# JediLightSwitch.net
KiCad netlist of a schematic drawn in EAGLE
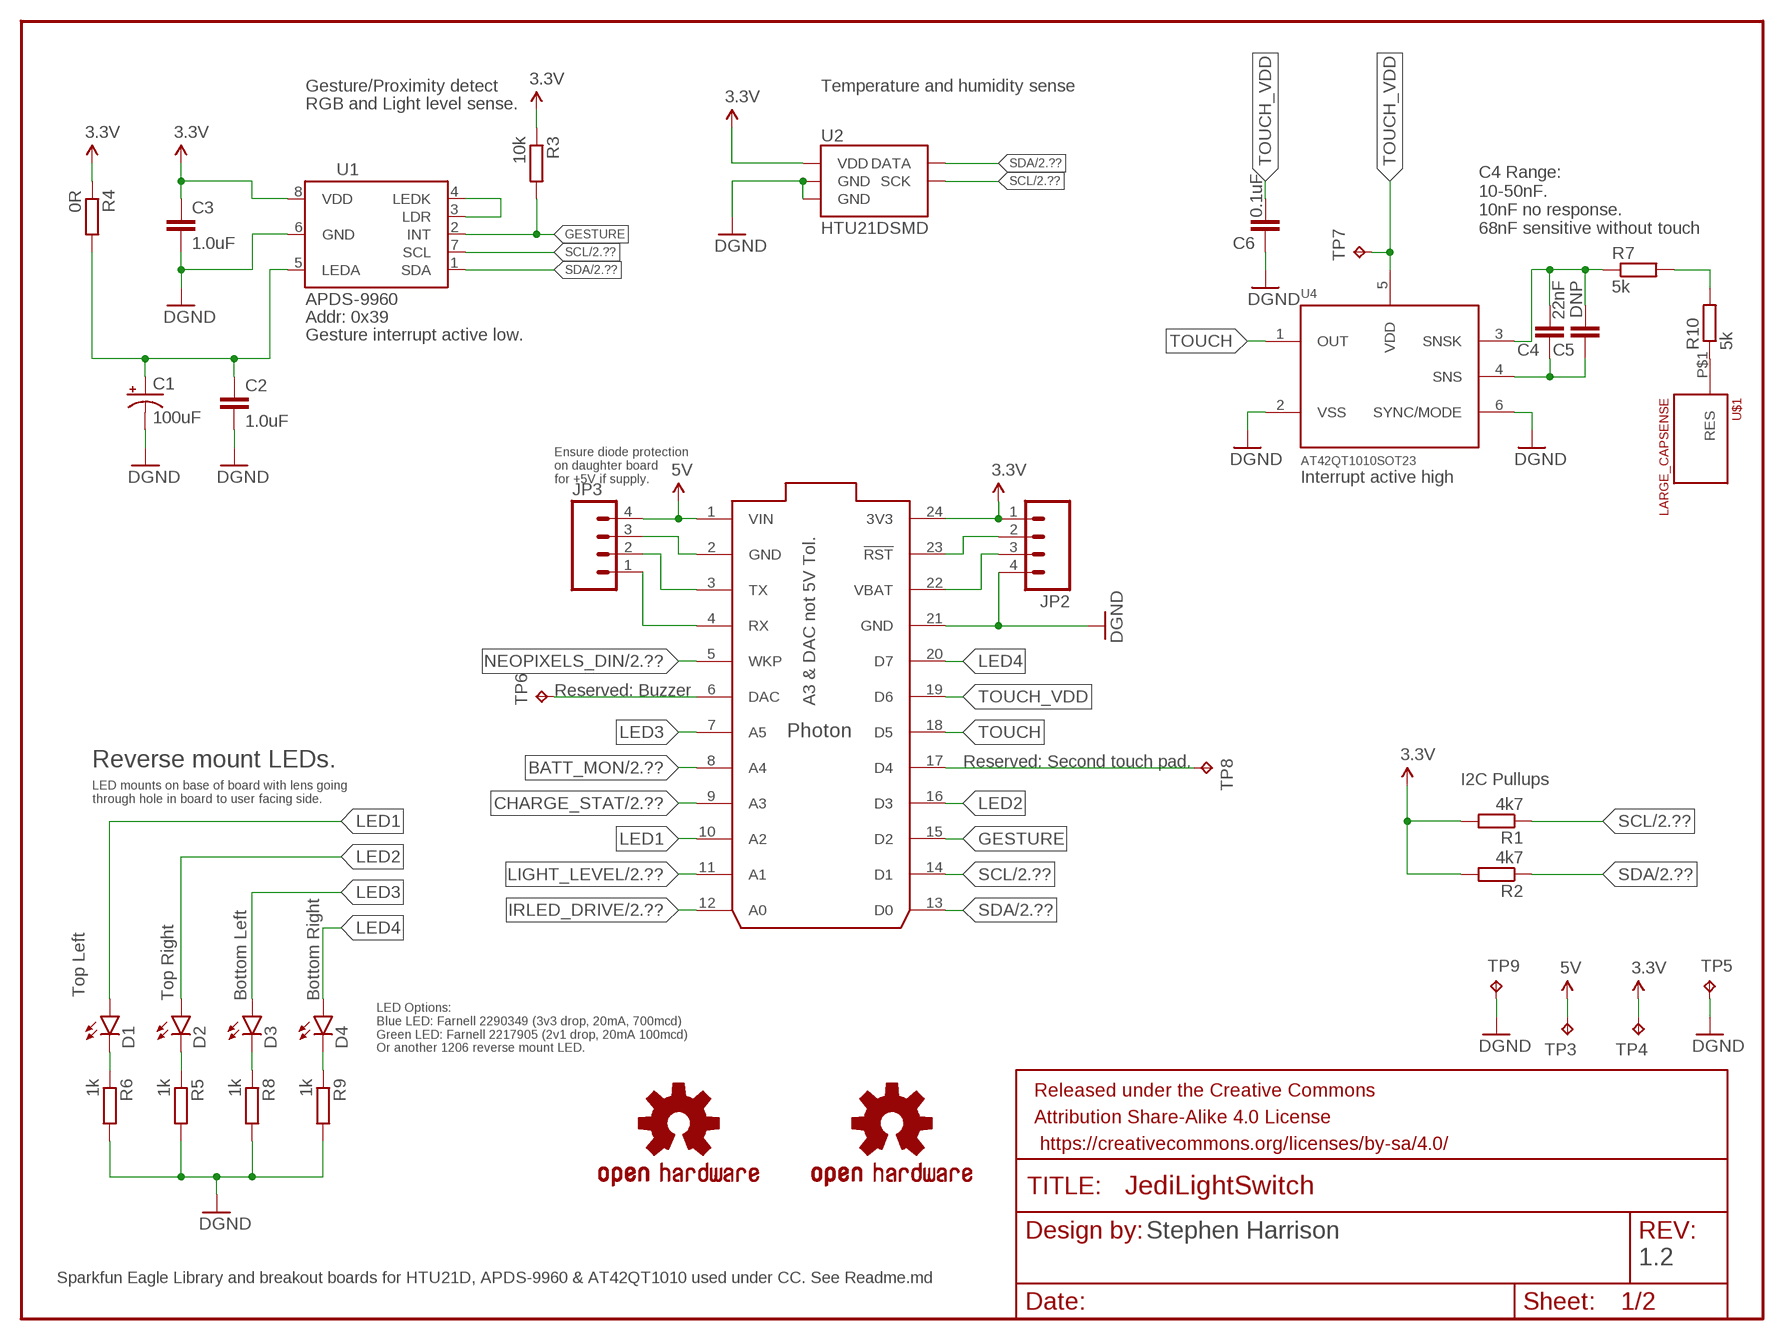
[diagram p0: schematic, sheet 1]
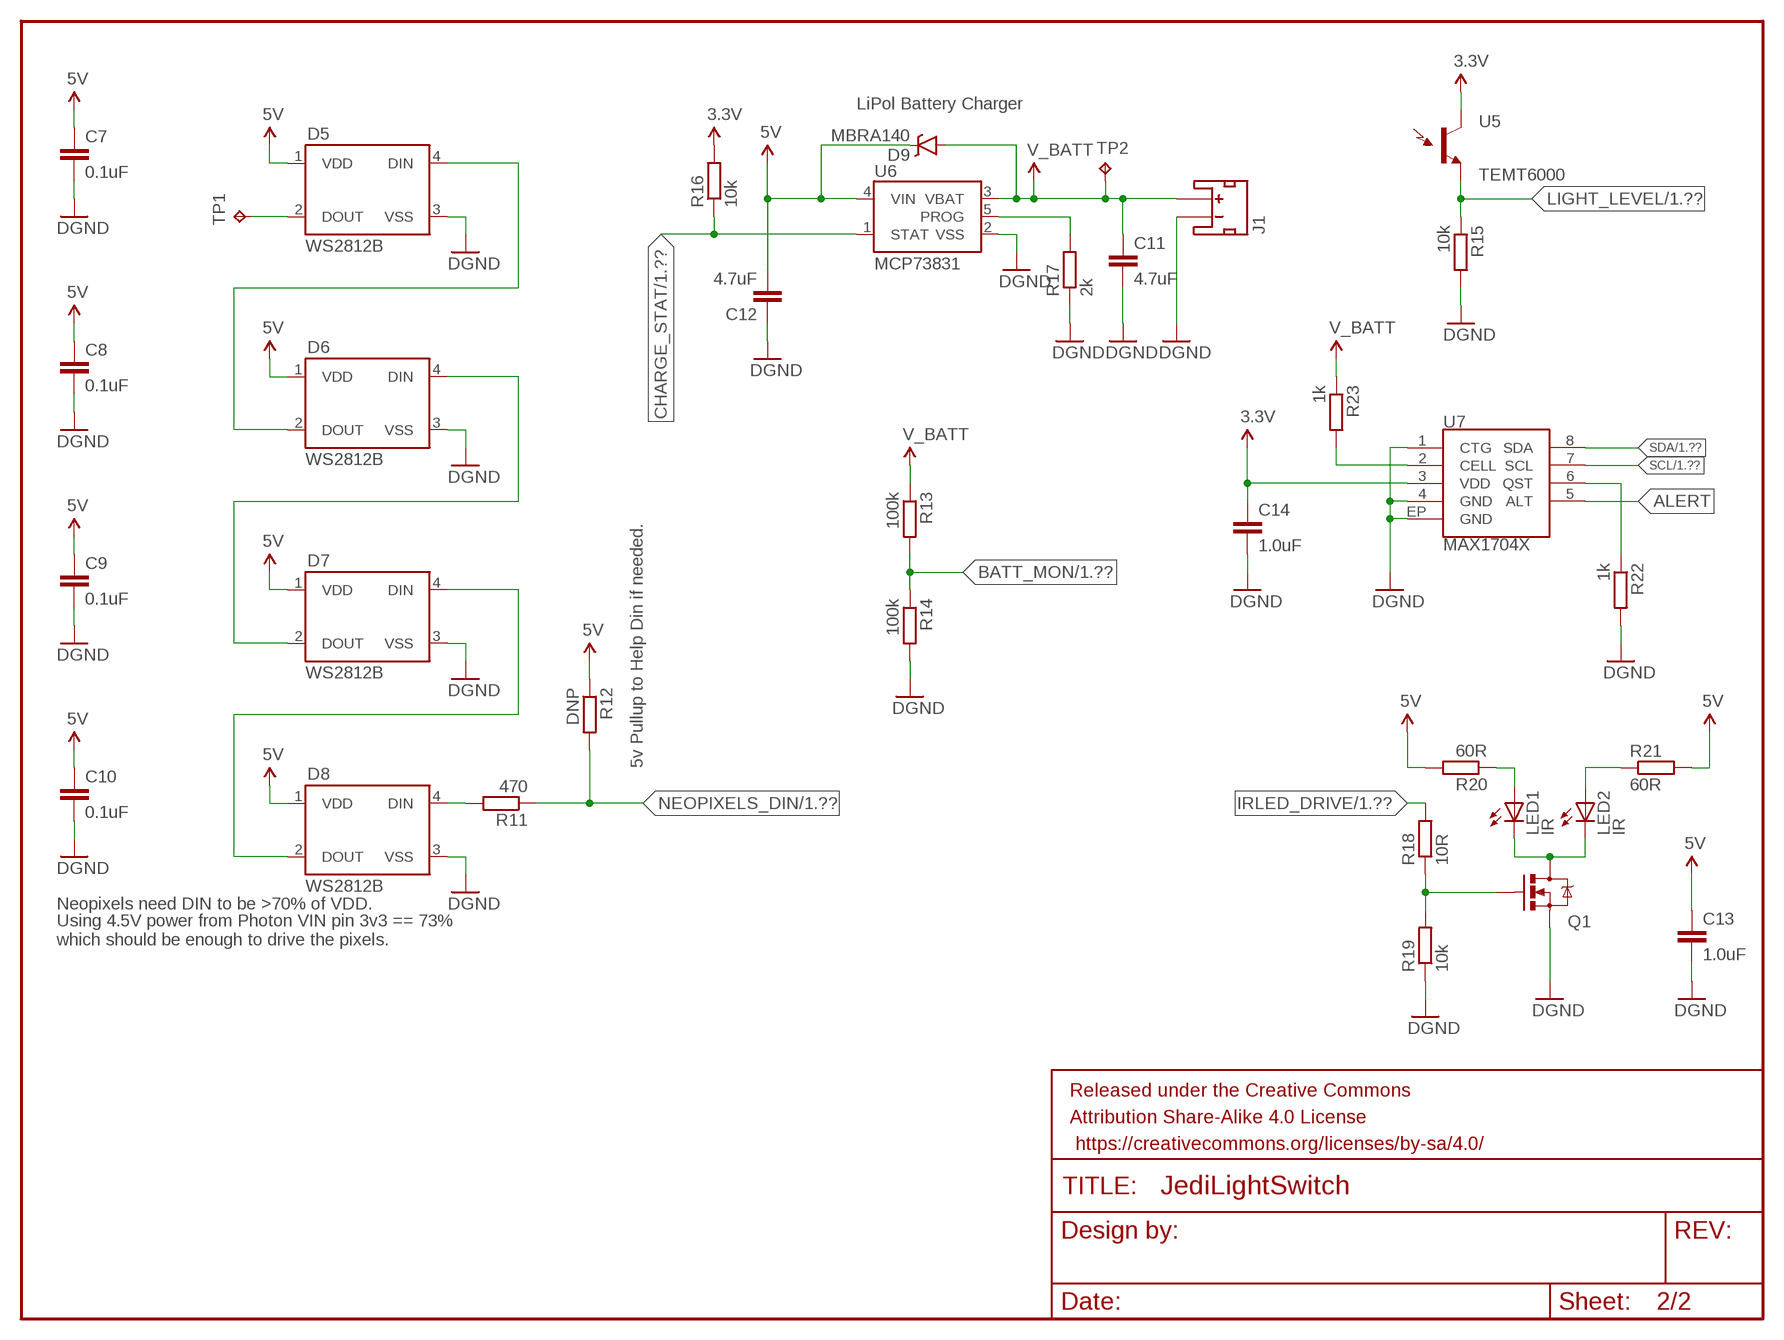
[diagram p1: schematic, sheet 2]

(export (version "E")
  (design (tool "Eeschema 10.0.6"))
  (components
    (comp (ref "C7")
      (value "0.1uF")
      (footprint "eagle-import:C0805")
      (libsource (lib "eagle-import") (part "C-EUC0805"))
    )
    (comp (ref "C8")
      (value "0.1uF")
      (footprint "eagle-import:C0805")
      (libsource (lib "eagle-import") (part "C-EUC0805"))
    )
    (comp (ref "C9")
      (value "0.1uF")
      (footprint "eagle-import:C0805")
      (libsource (lib "eagle-import") (part "C-EUC0805"))
    )
    (comp (ref "C10")
      (value "0.1uF")
      (footprint "eagle-import:C0805")
      (libsource (lib "eagle-import") (part "C-EUC0805"))
    )
    (comp (ref "C11")
      (value "4.7uF")
      (footprint "eagle-import:C0805")
      (libsource (lib "eagle-import") (part "C-EUC0805"))
    )
    (comp (ref "C12")
      (value "4.7uF")
      (footprint "eagle-import:C0805")
      (libsource (lib "eagle-import") (part "C-EUC0805"))
    )
    (comp (ref "C13")
      (value "1.0uF")
      (footprint "eagle-import:C0805")
      (libsource (lib "eagle-import") (part "C-EUC0805"))
    )
    (comp (ref "C14")
      (value "1.0uF")
      (footprint "eagle-import:C0805")
      (libsource (lib "eagle-import") (part "C-EUC0805"))
    )
    (comp (ref "D5")
      (value "WS2812B")
      (footprint "eagle-import:WS2812B")
      (libsource (lib "eagle-import") (part "WS2812B"))
    )
    (comp (ref "D6")
      (value "WS2812B")
      (footprint "eagle-import:WS2812B")
      (libsource (lib "eagle-import") (part "WS2812B"))
    )
    (comp (ref "D7")
      (value "WS2812B")
      (footprint "eagle-import:WS2812B")
      (libsource (lib "eagle-import") (part "WS2812B"))
    )
    (comp (ref "D8")
      (value "WS2812B")
      (footprint "eagle-import:WS2812B")
      (libsource (lib "eagle-import") (part "WS2812B"))
    )
    (comp (ref "D9")
      (value "MBRA140")
      (footprint "eagle-import:SMA-DIODE")
      (libsource (lib "eagle-import") (part "MBRA140"))
    )
    (comp (ref "FRAME1")
      (value "FRAME-LETTERNO_PACKAGE")
      (footprint "eagle-import:DUMMY")
      (fields (field (name "DESIGNER") "Nobody"))
      (libsource (lib "eagle-import") (part "FRAME-LETTERNO_PACKAGE"))
    )
    (comp (ref "J1")
      (value "JST_2MM_MALE")
      (footprint "eagle-import:JST-2-SMD")
      (libsource (lib "eagle-import") (part "JST_2MM_MALE"))
    )
    (comp (ref "LED1")
      (value "IR")
      (footprint "eagle-import:1206")
      (libsource (lib "eagle-import") (part "LEDSMT1206"))
    )
    (comp (ref "LED2")
      (value "IR")
      (footprint "eagle-import:1206")
      (libsource (lib "eagle-import") (part "LEDSMT1206"))
    )
    (comp (ref "Q1")
      (value "MOSFET-NCHANNELAO3404A")
      (footprint "eagle-import:SOT23-3")
      (libsource (lib "eagle-import") (part "MOSFET-NCHANNELAO3404A"))
    )
    (comp (ref "R11")
      (value "470")
      (footprint "eagle-import:R0805")
      (libsource (lib "eagle-import") (part "R-EU_R0805"))
    )
    (comp (ref "R12")
      (value "DNP")
      (footprint "eagle-import:R0805")
      (libsource (lib "eagle-import") (part "R-EU_R0805"))
    )
    (comp (ref "R13")
      (value "100k")
      (footprint "eagle-import:R0805")
      (libsource (lib "eagle-import") (part "R-EU_R0805"))
    )
    (comp (ref "R14")
      (value "100k")
      (footprint "eagle-import:R0805")
      (libsource (lib "eagle-import") (part "R-EU_R0805"))
    )
    (comp (ref "R15")
      (value "10k")
      (footprint "eagle-import:R0805")
      (libsource (lib "eagle-import") (part "R-EU_R0805"))
    )
    (comp (ref "R16")
      (value "10k")
      (footprint "eagle-import:R0805")
      (libsource (lib "eagle-import") (part "R-EU_R0805"))
    )
    (comp (ref "R17")
      (value "2k")
      (footprint "eagle-import:R0805")
      (libsource (lib "eagle-import") (part "R-EU_R0805"))
    )
    (comp (ref "R18")
      (value "10R")
      (footprint "eagle-import:R0805")
      (libsource (lib "eagle-import") (part "R-EU_R0805"))
    )
    (comp (ref "R19")
      (value "10k")
      (footprint "eagle-import:R0805")
      (libsource (lib "eagle-import") (part "R-EU_R0805"))
    )
    (comp (ref "R20")
      (value "60R")
      (footprint "eagle-import:R0805")
      (libsource (lib "eagle-import") (part "R-EU_R0805"))
    )
    (comp (ref "R21")
      (value "60R")
      (footprint "eagle-import:R0805")
      (libsource (lib "eagle-import") (part "R-EU_R0805"))
    )
    (comp (ref "R22")
      (value "1k")
      (footprint "eagle-import:R0805")
      (libsource (lib "eagle-import") (part "R-EU_R0805"))
    )
    (comp (ref "R23")
      (value "1k")
      (footprint "eagle-import:R0805")
      (libsource (lib "eagle-import") (part "R-EU_R0805"))
    )
    (comp (ref "TP1")
      (value "TPTP20R")
      (footprint "eagle-import:TP20R")
      (libsource (lib "eagle-import") (part "TPTP20R"))
    )
    (comp (ref "TP2")
      (value "TPTP20R")
      (footprint "eagle-import:TP20R")
      (libsource (lib "eagle-import") (part "TPTP20R"))
    )
    (comp (ref "U5")
      (value "TEMT6000")
      (footprint "eagle-import:TEMT6000-SEN")
      (libsource (lib "eagle-import") (part "LIGHTSENSORTEMT6000"))
    )
    (comp (ref "U6")
      (value "MCP73831")
      (footprint "eagle-import:SOT23-5")
      (libsource (lib "eagle-import") (part "MCP73831"))
    )
    (comp (ref "U7")
      (value "MAX1704X")
      (footprint "eagle-import:TDFN-8")
      (libsource (lib "eagle-import") (part "MAX1704X"))
    )
    (comp (ref "C1")
      (value "100uF")
      (footprint "eagle-import:EIA7343")
      (libsource (lib "eagle-import") (part "100UF-10V-10%(TANT)"))
    )
    (comp (ref "C2")
      (value "1.0uF")
      (footprint "eagle-import:C0805")
      (libsource (lib "eagle-import") (part "C-EUC0805"))
    )
    (comp (ref "C3")
      (value "1.0uF")
      (footprint "eagle-import:C0805")
      (libsource (lib "eagle-import") (part "C-EUC0805"))
    )
    (comp (ref "C4")
      (value "22nF")
      (footprint "eagle-import:C0805")
      (libsource (lib "eagle-import") (part "C-EUC0805"))
    )
    (comp (ref "C5")
      (value "DNP")
      (footprint "eagle-import:C0805")
      (libsource (lib "eagle-import") (part "C-EUC0805"))
    )
    (comp (ref "C6")
      (value "0.1uF")
      (footprint "eagle-import:C0805")
      (libsource (lib "eagle-import") (part "C-EUC0805"))
    )
    (comp (ref "D1")
      (value "LED1206-BOTTOM")
      (footprint "eagle-import:LED-1206-BOTTOM")
      (libsource (lib "eagle-import") (part "LED1206-BOTTOM"))
    )
    (comp (ref "D2")
      (value "LED1206-BOTTOM")
      (footprint "eagle-import:LED-1206-BOTTOM")
      (libsource (lib "eagle-import") (part "LED1206-BOTTOM"))
    )
    (comp (ref "D3")
      (value "LED1206-BOTTOM")
      (footprint "eagle-import:LED-1206-BOTTOM")
      (libsource (lib "eagle-import") (part "LED1206-BOTTOM"))
    )
    (comp (ref "D4")
      (value "LED1206-BOTTOM")
      (footprint "eagle-import:LED-1206-BOTTOM")
      (libsource (lib "eagle-import") (part "LED1206-BOTTOM"))
    )
    (comp (ref "FRAME2")
      (value "FRAME-LETTER")
      (footprint "eagle-import:CREATIVE_COMMONS")
      (libsource (lib "eagle-import") (part "FRAME-LETTER"))
    )
    (comp (ref "JP2")
      (value "M04SMD_STRAIGHT_COMBO")
      (footprint "eagle-import:1X04_SMD_STRAIGHT_COMBO")
      (libsource (lib "eagle-import") (part "M04SMD_STRAIGHT_COMBO"))
    )
    (comp (ref "JP3")
      (value "M04SMD_STRAIGHT_COMBO")
      (footprint "eagle-import:1X04_SMD_STRAIGHT_COMBO")
      (libsource (lib "eagle-import") (part "M04SMD_STRAIGHT_COMBO"))
    )
    (comp (ref "LOGO1")
      (value "OSHW-LOGOM")
      (footprint "eagle-import:OSHW-LOGO-M")
      (libsource (lib "eagle-import") (part "OSHW-LOGOM"))
    )
    (comp (ref "LOGO2")
      (value "OSHW-LOGOM")
      (footprint "eagle-import:OSHW-LOGO-M")
      (libsource (lib "eagle-import") (part "OSHW-LOGOM"))
    )
    (comp (ref "R1")
      (value "4k7")
      (footprint "eagle-import:R0805")
      (libsource (lib "eagle-import") (part "R-EU_R0805"))
    )
    (comp (ref "R2")
      (value "4k7")
      (footprint "eagle-import:R0805")
      (libsource (lib "eagle-import") (part "R-EU_R0805"))
    )
    (comp (ref "R3")
      (value "10k")
      (footprint "eagle-import:R0805")
      (libsource (lib "eagle-import") (part "R-EU_R0805"))
    )
    (comp (ref "R4")
      (value "0R")
      (footprint "eagle-import:R0805")
      (libsource (lib "eagle-import") (part "R-EU_R0805"))
    )
    (comp (ref "R5")
      (value "1k")
      (footprint "eagle-import:R0805")
      (libsource (lib "eagle-import") (part "R-EU_R0805"))
    )
    (comp (ref "R6")
      (value "1k")
      (footprint "eagle-import:R0805")
      (libsource (lib "eagle-import") (part "R-EU_R0805"))
    )
    (comp (ref "R7")
      (value "5k")
      (footprint "eagle-import:R0805")
      (libsource (lib "eagle-import") (part "R-EU_R0805"))
    )
    (comp (ref "R8")
      (value "1k")
      (footprint "eagle-import:R0805")
      (libsource (lib "eagle-import") (part "R-EU_R0805"))
    )
    (comp (ref "R9")
      (value "1k")
      (footprint "eagle-import:R0805")
      (libsource (lib "eagle-import") (part "R-EU_R0805"))
    )
    (comp (ref "R10")
      (value "5k")
      (footprint "eagle-import:R0805")
      (libsource (lib "eagle-import") (part "R-EU_R0805"))
    )
    (comp (ref "TP3")
      (value "TPTP20R")
      (footprint "eagle-import:TP20R")
      (libsource (lib "eagle-import") (part "TPTP20R"))
    )
    (comp (ref "TP4")
      (value "3v3")
      (footprint "eagle-import:TP20R")
      (libsource (lib "eagle-import") (part "TPTP20R"))
    )
    (comp (ref "TP5")
      (value "TPTP20R")
      (footprint "eagle-import:TP20R")
      (libsource (lib "eagle-import") (part "TPTP20R"))
    )
    (comp (ref "TP6")
      (value "TPTP20R")
      (footprint "eagle-import:TP20R")
      (libsource (lib "eagle-import") (part "TPTP20R"))
    )
    (comp (ref "TP7")
      (value "TPTP20R")
      (footprint "eagle-import:TP20R")
      (libsource (lib "eagle-import") (part "TPTP20R"))
    )
    (comp (ref "TP8")
      (value "TPTP20R")
      (footprint "eagle-import:TP20R")
      (libsource (lib "eagle-import") (part "TPTP20R"))
    )
    (comp (ref "TP9")
      (value "TPTP20R")
      (footprint "eagle-import:TP20R")
      (libsource (lib "eagle-import") (part "TPTP20R"))
    )
    (comp (ref "U$1")
      (value "LARGE_CAPSENSE")
      (footprint "eagle-import:LARGE_CAPSENSE")
      (libsource (lib "eagle-import") (part "LARGE_CAPSENSE"))
    )
    (comp (ref "U1")
      (value "APDS-9960")
      (footprint "eagle-import:APDS-9960")
      (libsource (lib "eagle-import") (part "APDS-9960"))
    )
    (comp (ref "U2")
      (value "HTU21DSMD")
      (footprint "eagle-import:HTU21D")
      (libsource (lib "eagle-import") (part "HTU21DSMD"))
    )
    (comp (ref "U3")
      (value "PHOTON_SMD")
      (footprint "eagle-import:PHOTON_SMD")
      (libsource (lib "eagle-import") (part "PHOTON_SMD"))
    )
    (comp (ref "U4")
      (value "AT42QT1010SOT23")
      (footprint "eagle-import:SOT23-6")
      (libsource (lib "eagle-import") (part "AT42QT1010SOT23"))
    )
  )
  (nets
    (net (code "1") (name "3.3V") (class "Default")
      (node (ref "C14") (pin "1") (pinfunction "1_1") (pintype "passive"))
      (node (ref "C3") (pin "1") (pinfunction "1_1") (pintype "passive"))
      (node (ref "JP2") (pin "1") (pinfunction "1_1") (pintype "passive"))
      (node (ref "R1") (pin "2") (pinfunction "2_2") (pintype "passive"))
      (node (ref "R16") (pin "2") (pinfunction "2_2") (pintype "passive"))
      (node (ref "R2") (pin "2") (pinfunction "2_2") (pintype "passive"))
      (node (ref "R3") (pin "1") (pinfunction "1_1") (pintype "passive"))
      (node (ref "R4") (pin "1") (pinfunction "1_1") (pintype "passive"))
      (node (ref "TP4") (pin "TP") (pinfunction "TP_TP") (pintype "input"))
      (node (ref "U1") (pin "8") (pinfunction "VDD_8") (pintype "bidirectional"))
      (node (ref "U2") (pin "VDD") (pinfunction "VDD_VDD") (pintype "power_in"))
      (node (ref "U3") (pin "24") (pinfunction "3V3_24") (pintype "power_in"))
      (node (ref "U5") (pin "COLLECTOR") (pinfunction "C1_COLLECTOR") (pintype "passive"))
      (node (ref "U7") (pin "3") (pinfunction "VDD_3") (pintype "bidirectional"))
    )
    (net (code "2") (name "5V") (class "Default")
      (node (ref "C10") (pin "1") (pinfunction "1_1") (pintype "passive"))
      (node (ref "C12") (pin "2") (pinfunction "2_2") (pintype "passive"))
      (node (ref "C13") (pin "1") (pinfunction "1_1") (pintype "passive"))
      (node (ref "C7") (pin "1") (pinfunction "1_1") (pintype "passive"))
      (node (ref "C8") (pin "1") (pinfunction "1_1") (pintype "passive"))
      (node (ref "C9") (pin "1") (pinfunction "1_1") (pintype "passive"))
      (node (ref "D5") (pin "1") (pinfunction "VDD_1") (pintype "power_in"))
      (node (ref "D6") (pin "1") (pinfunction "VDD_1") (pintype "power_in"))
      (node (ref "D7") (pin "1") (pinfunction "VDD_1") (pintype "power_in"))
      (node (ref "D8") (pin "1") (pinfunction "VDD_1") (pintype "power_in"))
      (node (ref "D9") (pin "C") (pinfunction "C_C") (pintype "passive"))
      (node (ref "JP3") (pin "4") (pinfunction "4_4") (pintype "passive"))
      (node (ref "R12") (pin "1") (pinfunction "1_1") (pintype "passive"))
      (node (ref "R20") (pin "2") (pinfunction "2_2") (pintype "passive"))
      (node (ref "R21") (pin "2") (pinfunction "2_2") (pintype "passive"))
      (node (ref "TP3") (pin "TP") (pinfunction "TP_TP") (pintype "input"))
      (node (ref "U3") (pin "1") (pinfunction "VIN_1") (pintype "power_in"))
      (node (ref "U6") (pin "4") (pinfunction "VIN_4") (pintype "power_in"))
    )
    (net (code "3") (name "ALERT") (class "Default")
      (node (ref "U7") (pin "5") (pinfunction "ALT_5") (pintype "bidirectional"))
    )
    (net (code "4") (name "BATT_MON") (class "Default")
      (node (ref "R13") (pin "2") (pinfunction "2_2") (pintype "passive"))
      (node (ref "R14") (pin "1") (pinfunction "1_1") (pintype "passive"))
      (node (ref "U3") (pin "8") (pinfunction "A4_8") (pintype "bidirectional"))
    )
    (net (code "5") (name "CHARGE_STAT") (class "Default")
      (node (ref "R16") (pin "1") (pinfunction "1_1") (pintype "passive"))
      (node (ref "U3") (pin "9") (pinfunction "A3_9") (pintype "bidirectional"))
      (node (ref "U6") (pin "1") (pinfunction "STAT_1") (pintype "output"))
    )
    (net (code "6") (name "GESTURE") (class "Default")
      (node (ref "R3") (pin "2") (pinfunction "2_2") (pintype "passive"))
      (node (ref "U1") (pin "2") (pinfunction "INT_2") (pintype "bidirectional"))
      (node (ref "U3") (pin "15") (pinfunction "D2_15") (pintype "bidirectional"))
    )
    (net (code "7") (name "GND") (class "Default")
      (node (ref "C1") (pin "C") (pinfunction "-_C") (pintype "passive"))
      (node (ref "C10") (pin "2") (pinfunction "2_2") (pintype "passive"))
      (node (ref "C11") (pin "2") (pinfunction "2_2") (pintype "passive"))
      (node (ref "C12") (pin "1") (pinfunction "1_1") (pintype "passive"))
      (node (ref "C13") (pin "2") (pinfunction "2_2") (pintype "passive"))
      (node (ref "C14") (pin "2") (pinfunction "2_2") (pintype "passive"))
      (node (ref "C2") (pin "2") (pinfunction "2_2") (pintype "passive"))
      (node (ref "C3") (pin "2") (pinfunction "2_2") (pintype "passive"))
      (node (ref "C6") (pin "1") (pinfunction "1_1") (pintype "passive"))
      (node (ref "C7") (pin "2") (pinfunction "2_2") (pintype "passive"))
      (node (ref "C8") (pin "2") (pinfunction "2_2") (pintype "passive"))
      (node (ref "C9") (pin "2") (pinfunction "2_2") (pintype "passive"))
      (node (ref "D5") (pin "3") (pinfunction "VSS_3") (pintype "power_in"))
      (node (ref "D6") (pin "3") (pinfunction "VSS_3") (pintype "power_in"))
      (node (ref "D7") (pin "3") (pinfunction "VSS_3") (pintype "power_in"))
      (node (ref "D8") (pin "3") (pinfunction "VSS_3") (pintype "power_in"))
      (node (ref "J1") (pin "1") (pinfunction "-_1") (pintype "bidirectional"))
      (node (ref "JP2") (pin "4") (pinfunction "4_4") (pintype "passive"))
      (node (ref "JP3") (pin "3") (pinfunction "3_3") (pintype "passive"))
      (node (ref "Q1") (pin "2") (pinfunction "S_2") (pintype "passive"))
      (node (ref "R14") (pin "2") (pinfunction "2_2") (pintype "passive"))
      (node (ref "R15") (pin "2") (pinfunction "2_2") (pintype "passive"))
      (node (ref "R17") (pin "1") (pinfunction "1_1") (pintype "passive"))
      (node (ref "R19") (pin "1") (pinfunction "1_1") (pintype "passive"))
      (node (ref "R22") (pin "2") (pinfunction "2_2") (pintype "passive"))
      (node (ref "R5") (pin "2") (pinfunction "2_2") (pintype "passive"))
      (node (ref "R6") (pin "2") (pinfunction "2_2") (pintype "passive"))
      (node (ref "R8") (pin "2") (pinfunction "2_2") (pintype "passive"))
      (node (ref "R9") (pin "2") (pinfunction "2_2") (pintype "passive"))
      (node (ref "TP5") (pin "TP") (pinfunction "TP_TP") (pintype "input"))
      (node (ref "TP9") (pin "TP") (pinfunction "TP_TP") (pintype "input"))
      (node (ref "U1") (pin "6") (pinfunction "GND_6") (pintype "bidirectional"))
      (node (ref "U2") (pin "7") (pinfunction "GND_7") (pintype "power_in"))
      (node (ref "U2") (pin "GND") (pinfunction "GND_GND") (pintype "power_in"))
      (node (ref "U3") (pin "2") (pinfunction "GND_2") (pintype "power_in"))
      (node (ref "U3") (pin "21") (pinfunction "GND_21") (pintype "power_in"))
      (node (ref "U4") (pin "2") (pinfunction "VSS_2") (pintype "bidirectional"))
      (node (ref "U4") (pin "6") (pinfunction "SYNC/MODE_6") (pintype "bidirectional"))
      (node (ref "U6") (pin "2") (pinfunction "VSS_2") (pintype "power_in"))
      (node (ref "U7") (pin "1") (pinfunction "CTG_1") (pintype "bidirectional"))
      (node (ref "U7") (pin "4") (pinfunction "GND_4") (pintype "bidirectional"))
      (node (ref "U7") (pin "EP") (pinfunction "GND_EP") (pintype "bidirectional"))
    )
    (net (code "8") (name "IRLED_DRIVE") (class "Default")
      (node (ref "R18") (pin "2") (pinfunction "2_2") (pintype "passive"))
      (node (ref "U3") (pin "12") (pinfunction "A0_12") (pintype "bidirectional"))
    )
    (net (code "9") (name "LED1") (class "Default")
      (node (ref "D1") (pin "A") (pinfunction "A_A") (pintype "passive"))
      (node (ref "U3") (pin "10") (pinfunction "A2_10") (pintype "bidirectional"))
    )
    (net (code "10") (name "LED2") (class "Default")
      (node (ref "D2") (pin "A") (pinfunction "A_A") (pintype "passive"))
      (node (ref "U3") (pin "16") (pinfunction "D3_16") (pintype "bidirectional"))
    )
    (net (code "11") (name "LED3") (class "Default")
      (node (ref "D3") (pin "A") (pinfunction "A_A") (pintype "passive"))
      (node (ref "U3") (pin "7") (pinfunction "A5_7") (pintype "bidirectional"))
    )
    (net (code "12") (name "LED4") (class "Default")
      (node (ref "D4") (pin "A") (pinfunction "A_A") (pintype "passive"))
      (node (ref "U3") (pin "20") (pinfunction "D7_20") (pintype "bidirectional"))
    )
    (net (code "13") (name "LIGHT_LEVEL") (class "Default")
      (node (ref "R15") (pin "1") (pinfunction "1_1") (pintype "passive"))
      (node (ref "U3") (pin "11") (pinfunction "A1_11") (pintype "bidirectional"))
      (node (ref "U5") (pin "EMITTER") (pinfunction "E1_EMITTER") (pintype "passive"))
    )
    (net (code "14") (name "NEOPIXELS_DIN") (class "Default")
      (node (ref "R11") (pin "1") (pinfunction "1_1") (pintype "passive"))
      (node (ref "R12") (pin "2") (pinfunction "2_2") (pintype "passive"))
      (node (ref "U3") (pin "5") (pinfunction "WKP_5") (pintype "bidirectional"))
    )
    (net (code "15") (name "Net-(C1-+)") (class "Default")
      (node (ref "C1") (pin "A") (pinfunction "+_A") (pintype "passive"))
      (node (ref "C2") (pin "1") (pinfunction "1_1") (pintype "passive"))
      (node (ref "R4") (pin "2") (pinfunction "2_2") (pintype "passive"))
      (node (ref "U1") (pin "5") (pinfunction "LEDA_5") (pintype "bidirectional"))
    )
    (net (code "16") (name "Net-(D1-PadC)") (class "Default")
      (node (ref "D1") (pin "C") (pinfunction "C_C") (pintype "passive"))
      (node (ref "R6") (pin "1") (pinfunction "1_1") (pintype "passive"))
    )
    (net (code "17") (name "Net-(D2-PadC)") (class "Default")
      (node (ref "D2") (pin "C") (pinfunction "C_C") (pintype "passive"))
      (node (ref "R5") (pin "1") (pinfunction "1_1") (pintype "passive"))
    )
    (net (code "18") (name "Net-(D3-PadC)") (class "Default")
      (node (ref "D3") (pin "C") (pinfunction "C_C") (pintype "passive"))
      (node (ref "R8") (pin "1") (pinfunction "1_1") (pintype "passive"))
    )
    (net (code "19") (name "Net-(D4-PadC)") (class "Default")
      (node (ref "D4") (pin "C") (pinfunction "C_C") (pintype "passive"))
      (node (ref "R9") (pin "1") (pinfunction "1_1") (pintype "passive"))
    )
    (net (code "20") (name "Net-(D5-DIN)") (class "Default")
      (node (ref "D5") (pin "4") (pinfunction "DIN_4") (pintype "input"))
      (node (ref "D6") (pin "2") (pinfunction "DOUT_2") (pintype "output"))
    )
    (net (code "21") (name "Net-(D5-DOUT)") (class "Default")
      (node (ref "D5") (pin "2") (pinfunction "DOUT_2") (pintype "output"))
      (node (ref "TP1") (pin "TP") (pinfunction "TP_TP") (pintype "input"))
    )
    (net (code "22") (name "Net-(D6-DIN)") (class "Default")
      (node (ref "D6") (pin "4") (pinfunction "DIN_4") (pintype "input"))
      (node (ref "D7") (pin "2") (pinfunction "DOUT_2") (pintype "output"))
    )
    (net (code "23") (name "Net-(D7-DIN)") (class "Default")
      (node (ref "D7") (pin "4") (pinfunction "DIN_4") (pintype "input"))
      (node (ref "D8") (pin "2") (pinfunction "DOUT_2") (pintype "output"))
    )
    (net (code "24") (name "Net-(D8-DIN)") (class "Default")
      (node (ref "D8") (pin "4") (pinfunction "DIN_4") (pintype "input"))
      (node (ref "R11") (pin "2") (pinfunction "2_2") (pintype "passive"))
    )
    (net (code "25") (name "Net-(LED1-PadA)") (class "Default")
      (node (ref "LED1") (pin "A") (pinfunction "A_A") (pintype "passive"))
      (node (ref "R20") (pin "1") (pinfunction "1_1") (pintype "passive"))
    )
    (net (code "26") (name "Net-(LED2-PadA)") (class "Default")
      (node (ref "LED2") (pin "A") (pinfunction "A_A") (pintype "passive"))
      (node (ref "R21") (pin "1") (pinfunction "1_1") (pintype "passive"))
    )
    (net (code "27") (name "Net-(Q1-D)") (class "Default")
      (node (ref "LED1") (pin "C") (pinfunction "C_C") (pintype "passive"))
      (node (ref "LED2") (pin "C") (pinfunction "C_C") (pintype "passive"))
      (node (ref "Q1") (pin "3") (pinfunction "D_3") (pintype "passive"))
    )
    (net (code "28") (name "Net-(Q1-G)") (class "Default")
      (node (ref "Q1") (pin "1") (pinfunction "G_1") (pintype "passive"))
      (node (ref "R18") (pin "1") (pinfunction "1_1") (pintype "passive"))
      (node (ref "R19") (pin "2") (pinfunction "2_2") (pintype "passive"))
    )
    (net (code "29") (name "Net-(R10-Pad2)") (class "Default")
      (node (ref "R10") (pin "2") (pinfunction "2_2") (pintype "passive"))
      (node (ref "R7") (pin "2") (pinfunction "2_2") (pintype "passive"))
    )
    (net (code "30") (name "Net-(U$1-RES)") (class "Default")
      (node (ref "R10") (pin "1") (pinfunction "1_1") (pintype "passive"))
      (node (ref "U$1") (pin "P$1") (pinfunction "RES_P$1") (pintype "bidirectional"))
    )
    (net (code "31") (name "Net-(U1-LDR)") (class "Default")
      (node (ref "U1") (pin "3") (pinfunction "LDR_3") (pintype "bidirectional"))
      (node (ref "U1") (pin "4") (pinfunction "LEDK_4") (pintype "bidirectional"))
    )
    (net (code "32") (name "Net-(U3A-D4)") (class "Default")
      (node (ref "TP8") (pin "TP") (pinfunction "TP_TP") (pintype "input"))
      (node (ref "U3") (pin "17") (pinfunction "D4_17") (pintype "bidirectional"))
    )
    (net (code "33") (name "Net-(U3A-DAC)") (class "Default")
      (node (ref "TP6") (pin "TP") (pinfunction "TP_TP") (pintype "input"))
      (node (ref "U3") (pin "6") (pinfunction "DAC_6") (pintype "bidirectional"))
    )
    (net (code "34") (name "Net-(U3A-RX)") (class "Default")
      (node (ref "JP3") (pin "1") (pinfunction "1_1") (pintype "passive"))
      (node (ref "U3") (pin "4") (pinfunction "RX_4") (pintype "bidirectional"))
    )
    (net (code "35") (name "Net-(U3A-TX)") (class "Default")
      (node (ref "JP3") (pin "2") (pinfunction "2_2") (pintype "passive"))
      (node (ref "U3") (pin "3") (pinfunction "TX_3") (pintype "bidirectional"))
    )
    (net (code "36") (name "Net-(U3A-VBAT)") (class "Default")
      (node (ref "JP2") (pin "3") (pinfunction "3_3") (pintype "passive"))
      (node (ref "U3") (pin "22") (pinfunction "VBAT_22") (pintype "power_in"))
    )
    (net (code "37") (name "Net-(U3A-~{RST})") (class "Default")
      (node (ref "JP2") (pin "2") (pinfunction "2_2") (pintype "passive"))
      (node (ref "U3") (pin "23") (pinfunction "~{RST}_23") (pintype "bidirectional"))
    )
    (net (code "38") (name "Net-(U4-SNS)") (class "Default")
      (node (ref "C4") (pin "1") (pinfunction "1_1") (pintype "passive"))
      (node (ref "C5") (pin "1") (pinfunction "1_1") (pintype "passive"))
      (node (ref "U4") (pin "4") (pinfunction "SNS_4") (pintype "bidirectional"))
    )
    (net (code "39") (name "Net-(U4-SNSK)") (class "Default")
      (node (ref "C4") (pin "2") (pinfunction "2_2") (pintype "passive"))
      (node (ref "C5") (pin "2") (pinfunction "2_2") (pintype "passive"))
      (node (ref "R7") (pin "1") (pinfunction "1_1") (pintype "passive"))
      (node (ref "U4") (pin "3") (pinfunction "SNSK_3") (pintype "bidirectional"))
    )
    (net (code "40") (name "Net-(U6-PROG)") (class "Default")
      (node (ref "R17") (pin "2") (pinfunction "2_2") (pintype "passive"))
      (node (ref "U6") (pin "5") (pinfunction "PROG_5") (pintype "input"))
    )
    (net (code "41") (name "Net-(U7-CELL)") (class "Default")
      (node (ref "R23") (pin "2") (pinfunction "2_2") (pintype "passive"))
      (node (ref "U7") (pin "2") (pinfunction "CELL_2") (pintype "bidirectional"))
    )
    (net (code "42") (name "Net-(U7-QST)") (class "Default")
      (node (ref "R22") (pin "1") (pinfunction "1_1") (pintype "passive"))
      (node (ref "U7") (pin "6") (pinfunction "QST_6") (pintype "bidirectional"))
    )
    (net (code "43") (name "SCL") (class "Default")
      (node (ref "R1") (pin "1") (pinfunction "1_1") (pintype "passive"))
      (node (ref "U1") (pin "7") (pinfunction "SCL_7") (pintype "bidirectional"))
      (node (ref "U2") (pin "SCK") (pinfunction "SCK_SCK") (pintype "input"))
      (node (ref "U3") (pin "14") (pinfunction "D1_14") (pintype "bidirectional"))
      (node (ref "U7") (pin "7") (pinfunction "SCL_7") (pintype "bidirectional"))
    )
    (net (code "44") (name "SDA") (class "Default")
      (node (ref "R2") (pin "1") (pinfunction "1_1") (pintype "passive"))
      (node (ref "U1") (pin "1") (pinfunction "SDA_1") (pintype "bidirectional"))
      (node (ref "U2") (pin "DATA") (pinfunction "DATA_DATA") (pintype "bidirectional"))
      (node (ref "U3") (pin "13") (pinfunction "D0_13") (pintype "bidirectional"))
      (node (ref "U7") (pin "8") (pinfunction "SDA_8") (pintype "bidirectional"))
    )
    (net (code "45") (name "TOUCH") (class "Default")
      (node (ref "U3") (pin "18") (pinfunction "D5_18") (pintype "bidirectional"))
      (node (ref "U4") (pin "1") (pinfunction "OUT_1") (pintype "bidirectional"))
    )
    (net (code "46") (name "TOUCH_VDD") (class "Default")
      (node (ref "C6") (pin "2") (pinfunction "2_2") (pintype "passive"))
      (node (ref "TP7") (pin "TP") (pinfunction "TP_TP") (pintype "input"))
      (node (ref "U3") (pin "19") (pinfunction "D6_19") (pintype "bidirectional"))
      (node (ref "U4") (pin "5") (pinfunction "VDD_5") (pintype "bidirectional"))
    )
    (net (code "47") (name "V_BATT") (class "Default")
      (node (ref "C11") (pin "1") (pinfunction "1_1") (pintype "passive"))
      (node (ref "D9") (pin "A") (pinfunction "A_A") (pintype "passive"))
      (node (ref "J1") (pin "2") (pinfunction "+_2") (pintype "bidirectional"))
      (node (ref "R13") (pin "1") (pinfunction "1_1") (pintype "passive"))
      (node (ref "R23") (pin "1") (pinfunction "1_1") (pintype "passive"))
      (node (ref "TP2") (pin "TP") (pinfunction "TP_TP") (pintype "input"))
      (node (ref "U6") (pin "3") (pinfunction "VBAT_3") (pintype "power_in"))
    )
    (net (code "48") (name "unconnected-(J1-PAD1-PadNC1)") (class "Default")
      (node (ref "J1") (pin "NC1") (pinfunction "PAD1_NC1") (pintype "bidirectional"))
    )
    (net (code "49") (name "unconnected-(J1-PAD2-PadNC2)") (class "Default")
      (node (ref "J1") (pin "NC2") (pinfunction "PAD2_NC2") (pintype "bidirectional"))
    )
  )
)
